# Nomi_s_Smart_Socket_V1.net
KiCad netlist of a schematic drawn in EAGLE
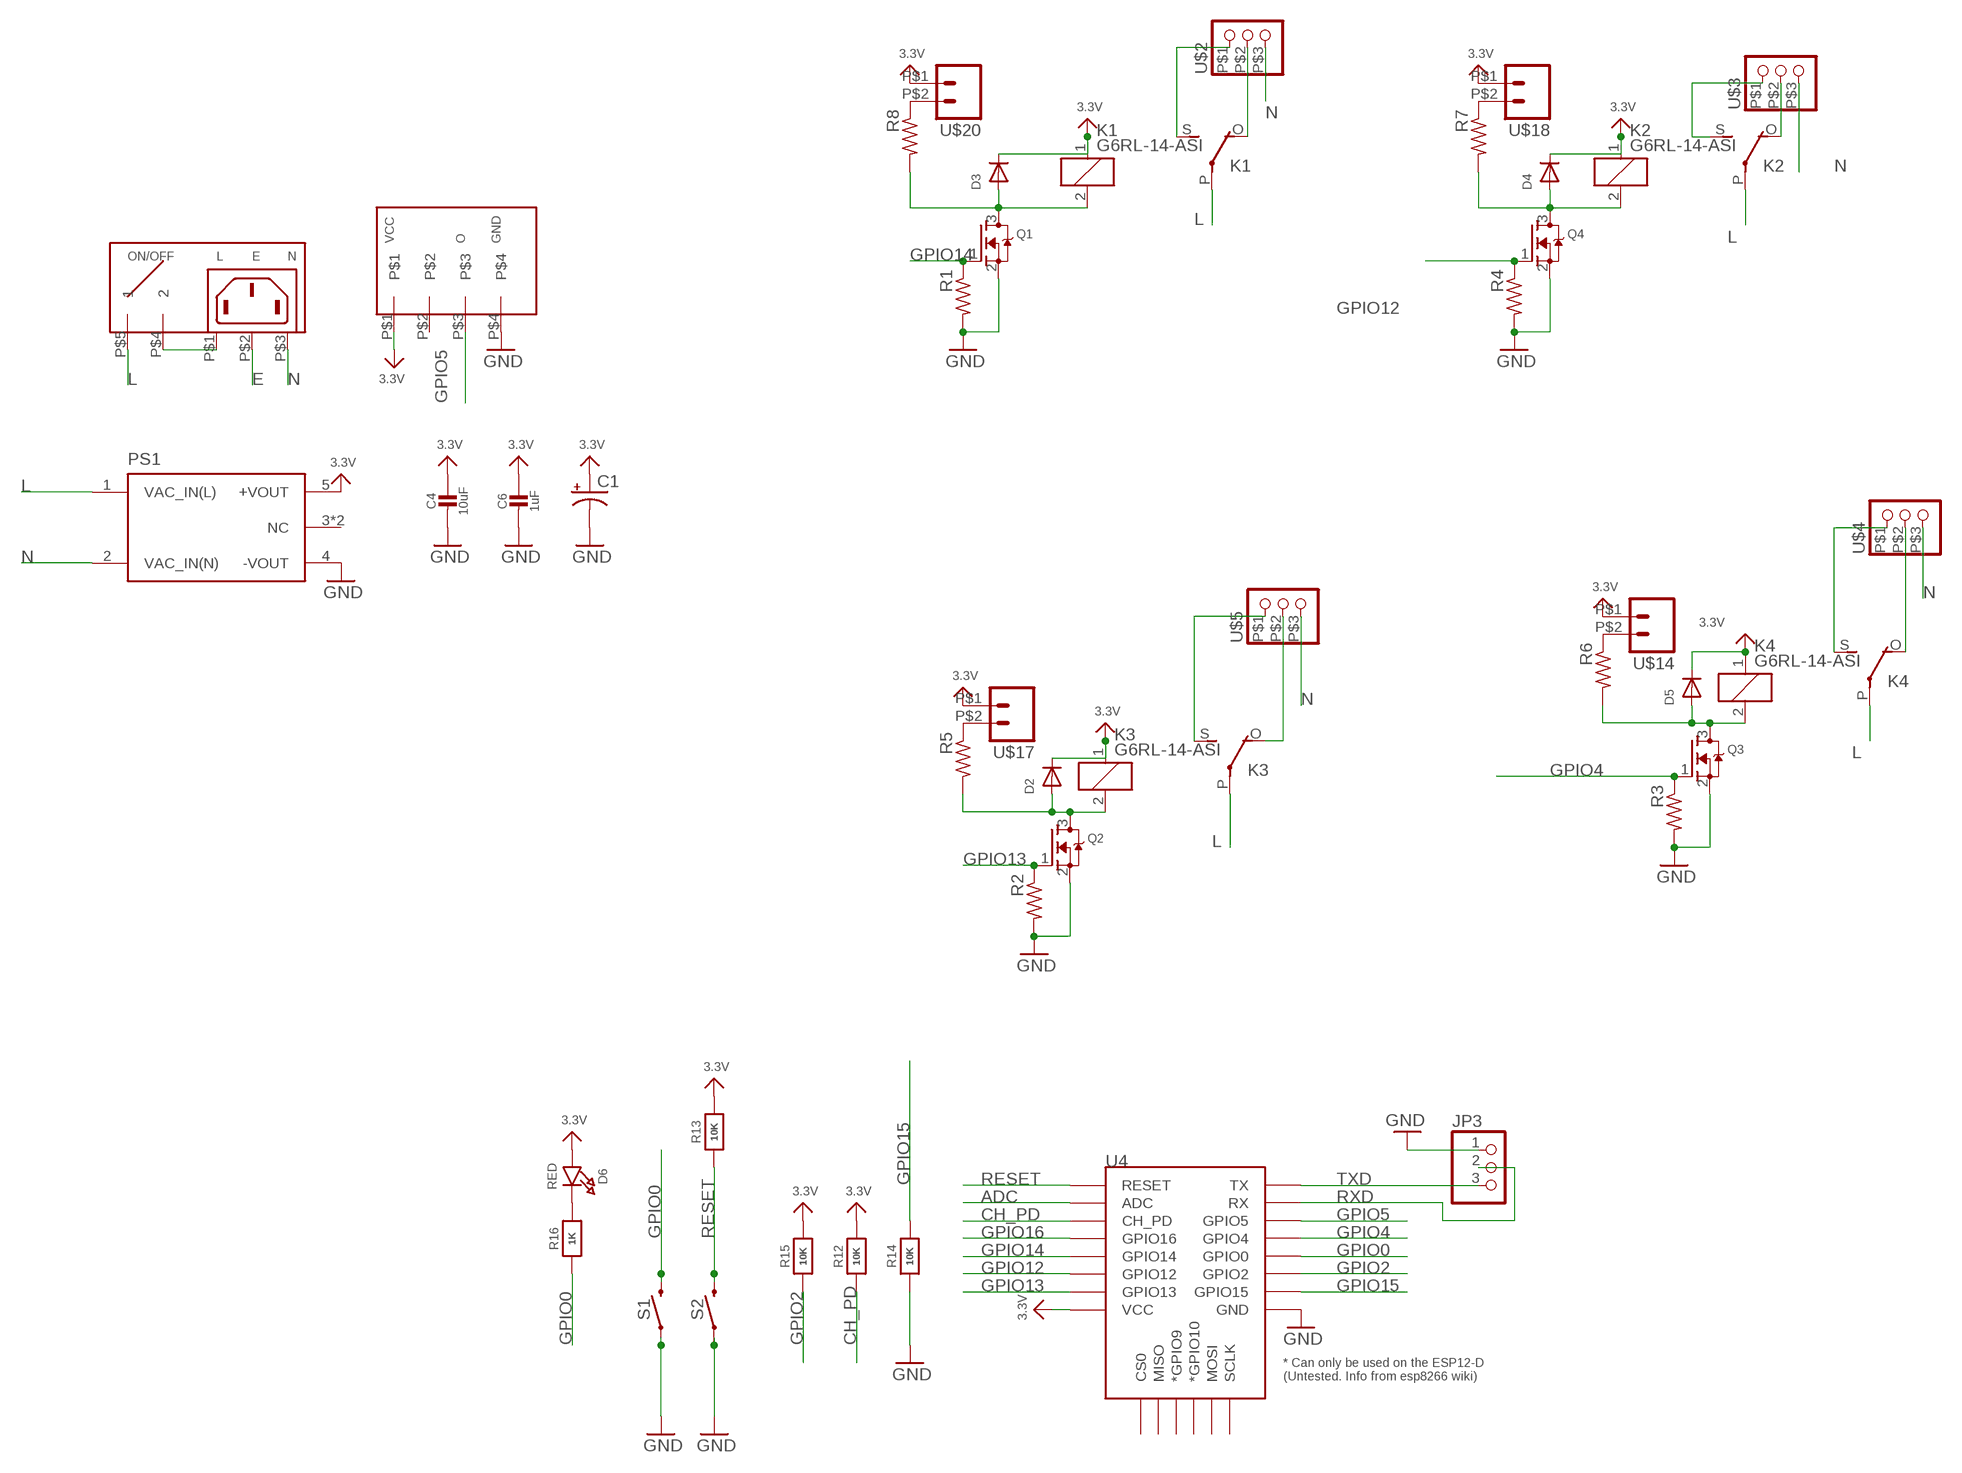
[diagram p0: schematic, sheet 1]

(export (version "E")
  (design (tool "Eeschema 10.0.6"))
  (components
    (comp (ref "C1")
      (value "CPOL-USE5-10.5")
      (footprint "eagle-import:E5-10,5")
      (libsource (lib "eagle-import") (part "CPOL-USE5-10.5"))
    )
    (comp (ref "C4")
      (value "10uF")
      (footprint "eagle-import:_0805")
      (libsource (lib "eagle-import") (part "CAP_CERAMIC_0805"))
    )
    (comp (ref "C6")
      (value "1uF")
      (footprint "eagle-import:_0603")
      (libsource (lib "eagle-import") (part "CAP_CERAMIC_0603"))
    )
    (comp (ref "D2")
      (value "DIODE_SOD-123FL")
      (footprint "eagle-import:SOD-123FL")
      (libsource (lib "eagle-import") (part "DIODE_SOD-123FL"))
    )
    (comp (ref "D3")
      (value "DIODE_SOD-123FL")
      (footprint "eagle-import:SOD-123FL")
      (libsource (lib "eagle-import") (part "DIODE_SOD-123FL"))
    )
    (comp (ref "D4")
      (value "DIODE_SOD-123FL")
      (footprint "eagle-import:SOD-123FL")
      (libsource (lib "eagle-import") (part "DIODE_SOD-123FL"))
    )
    (comp (ref "D5")
      (value "DIODE_SOD-123FL")
      (footprint "eagle-import:SOD-123FL")
      (libsource (lib "eagle-import") (part "DIODE_SOD-123FL"))
    )
    (comp (ref "D6")
      (value "RED")
      (footprint "eagle-import:CHIPLED_0805_NOOUTLINE")
      (libsource (lib "eagle-import") (part "LED0805_NOOUTLINE"))
    )
    (comp (ref "JP3")
      (value "PINHD-1X3")
      (footprint "eagle-import:1X03")
      (libsource (lib "eagle-import") (part "PINHD-1X3"))
    )
    (comp (ref "K1")
      (value "G6RL-14-ASI")
      (footprint "eagle-import:G6RW")
      (libsource (lib "eagle-import") (part "G6RL-14-ASI"))
    )
    (comp (ref "K2")
      (value "G6RL-14-ASI")
      (footprint "eagle-import:G6RW")
      (libsource (lib "eagle-import") (part "G6RL-14-ASI"))
    )
    (comp (ref "K3")
      (value "G6RL-14-ASI")
      (footprint "eagle-import:G6RW")
      (libsource (lib "eagle-import") (part "G6RL-14-ASI"))
    )
    (comp (ref "K4")
      (value "G6RL-14-ASI")
      (footprint "eagle-import:G6RW")
      (libsource (lib "eagle-import") (part "G6RL-14-ASI"))
    )
    (comp (ref "PS1")
      (value "RAC04-3.3SGBRAC04-3.3SGB-3D")
      (footprint "eagle-import:DIP1778W80P508L3670H1500Q6B")
      (libsource (lib "eagle-import") (part "RAC04-3.3SGBRAC04-3.3SGB-3D"))
    )
    (comp (ref "Q1")
      (value "MOSFET-NREFLOW")
      (footprint "eagle-import:SOT23")
      (libsource (lib "eagle-import") (part "MOSFET-NREFLOW"))
    )
    (comp (ref "Q2")
      (value "MOSFET-NREFLOW")
      (footprint "eagle-import:SOT23")
      (libsource (lib "eagle-import") (part "MOSFET-NREFLOW"))
    )
    (comp (ref "Q3")
      (value "MOSFET-NREFLOW")
      (footprint "eagle-import:SOT23")
      (libsource (lib "eagle-import") (part "MOSFET-NREFLOW"))
    )
    (comp (ref "Q4")
      (value "MOSFET-NREFLOW")
      (footprint "eagle-import:SOT23")
      (libsource (lib "eagle-import") (part "MOSFET-NREFLOW"))
    )
    (comp (ref "R1")
      (value "10k")
      (footprint "eagle-import:R0603")
      (libsource (lib "eagle-import") (part "R-US_R0603"))
    )
    (comp (ref "R2")
      (value "10k")
      (footprint "eagle-import:R0603")
      (libsource (lib "eagle-import") (part "R-US_R0603"))
    )
    (comp (ref "R3")
      (value "10k")
      (footprint "eagle-import:R0603")
      (libsource (lib "eagle-import") (part "R-US_R0603"))
    )
    (comp (ref "R4")
      (value "10k")
      (footprint "eagle-import:R0603")
      (libsource (lib "eagle-import") (part "R-US_R0603"))
    )
    (comp (ref "R5")
      (value "22")
      (footprint "eagle-import:R0603")
      (libsource (lib "eagle-import") (part "R-US_R0603"))
    )
    (comp (ref "R6")
      (value "22")
      (footprint "eagle-import:R0603")
      (libsource (lib "eagle-import") (part "R-US_R0603"))
    )
    (comp (ref "R7")
      (value "22")
      (footprint "eagle-import:R0603")
      (libsource (lib "eagle-import") (part "R-US_R0603"))
    )
    (comp (ref "R8")
      (value "22")
      (footprint "eagle-import:R0603")
      (libsource (lib "eagle-import") (part "R-US_R0603"))
    )
    (comp (ref "R12")
      (value "10K")
      (footprint "eagle-import:_0603")
      (libsource (lib "eagle-import") (part "RESISTOR_0603"))
    )
    (comp (ref "R13")
      (value "10K")
      (footprint "eagle-import:_0603")
      (libsource (lib "eagle-import") (part "RESISTOR_0603"))
    )
    (comp (ref "R14")
      (value "10K")
      (footprint "eagle-import:_0603")
      (libsource (lib "eagle-import") (part "RESISTOR_0603"))
    )
    (comp (ref "R15")
      (value "10K")
      (footprint "eagle-import:_0603")
      (libsource (lib "eagle-import") (part "RESISTOR_0603"))
    )
    (comp (ref "R16")
      (value "1K")
      (footprint "eagle-import:_0603")
      (libsource (lib "eagle-import") (part "RESISTOR_0603"))
    )
    (comp (ref "S1")
      (value "MOMENTARY-SWITCH-SPST-SMD-4.6X2.8MM")
      (footprint "eagle-import:TACTILE_SWITCH_SMD_4.6X2.8MM")
      (libsource (lib "eagle-import") (part "MOMENTARY-SWITCH-SPST-SMD-4.6X2.8MM"))
    )
    (comp (ref "S2")
      (value "MOMENTARY-SWITCH-SPST-SMD-4.6X2.8MM")
      (footprint "eagle-import:TACTILE_SWITCH_SMD_4.6X2.8MM")
      (libsource (lib "eagle-import") (part "MOMENTARY-SWITCH-SPST-SMD-4.6X2.8MM"))
    )
    (comp (ref "U$1")
      (value "AC-CONN-WITH-SWITCH")
      (footprint "eagle-import:AC-CONN-WITH-SWITCH")
      (libsource (lib "eagle-import") (part "AC-CONN-WITH-SWITCH"))
    )
    (comp (ref "U$2")
      (value "TERM-BLOCK-3POS-5MM5MM")
      (footprint "eagle-import:TERM-BLOCK-3POS-5MM")
      (libsource (lib "eagle-import") (part "TERM-BLOCK-3POS-5MM5MM"))
    )
    (comp (ref "U$3")
      (value "TERM-BLOCK-3POS-5MM5MM")
      (footprint "eagle-import:TERM-BLOCK-3POS-5MM")
      (libsource (lib "eagle-import") (part "TERM-BLOCK-3POS-5MM5MM"))
    )
    (comp (ref "U$4")
      (value "TERM-BLOCK-3POS-5MM5MM")
      (footprint "eagle-import:TERM-BLOCK-3POS-5MM")
      (libsource (lib "eagle-import") (part "TERM-BLOCK-3POS-5MM5MM"))
    )
    (comp (ref "U$5")
      (value "TERM-BLOCK-3POS-5MM5MM")
      (footprint "eagle-import:TERM-BLOCK-3POS-5MM")
      (libsource (lib "eagle-import") (part "TERM-BLOCK-3POS-5MM5MM"))
    )
    (comp (ref "U$13")
      (value "DHT22")
      (footprint "eagle-import:DHT22")
      (libsource (lib "eagle-import") (part "DHT22"))
    )
    (comp (ref "U$14")
      (value "TERMINAL-BLOCK-2POS-2.54MM")
      (footprint "eagle-import:TERMINAL-BLOCK-2POS-2.54MM")
      (libsource (lib "eagle-import") (part "TERMINAL-BLOCK-2POS-2.54MM"))
    )
    (comp (ref "U$17")
      (value "TERMINAL-BLOCK-2POS-2.54MM")
      (footprint "eagle-import:TERMINAL-BLOCK-2POS-2.54MM")
      (libsource (lib "eagle-import") (part "TERMINAL-BLOCK-2POS-2.54MM"))
    )
    (comp (ref "U$18")
      (value "TERMINAL-BLOCK-2POS-2.54MM")
      (footprint "eagle-import:TERMINAL-BLOCK-2POS-2.54MM")
      (libsource (lib "eagle-import") (part "TERMINAL-BLOCK-2POS-2.54MM"))
    )
    (comp (ref "U$20")
      (value "TERMINAL-BLOCK-2POS-2.54MM")
      (footprint "eagle-import:TERMINAL-BLOCK-2POS-2.54MM")
      (libsource (lib "eagle-import") (part "TERMINAL-BLOCK-2POS-2.54MM"))
    )
    (comp (ref "U4")
      (value "ESP12FSMD")
      (footprint "eagle-import:ESP12F")
      (libsource (lib "eagle-import") (part "ESP12FSMD"))
    )
  )
  (nets
    (net (code "1") (name "/ADC") (class "Default")
      (node (ref "U4") (pin "ADC") (pinfunction "ADC_ADC") (pintype "bidirectional"))
    )
    (net (code "2") (name "/CH_PD") (class "Default")
      (node (ref "R12") (pin "1") (pinfunction "1_1") (pintype "passive"))
      (node (ref "U4") (pin "EN") (pinfunction "CH_PD_EN") (pintype "bidirectional"))
    )
    (net (code "3") (name "/E") (class "Default")
      (node (ref "U$1") (pin "P$2") (pinfunction "EARTH_P$2") (pintype "passive"))
    )
    (net (code "4") (name "/GPIO0") (class "Default")
      (node (ref "R16") (pin "1") (pinfunction "1_1") (pintype "passive"))
      (node (ref "S1") (pin "3") (pinfunction "2_3") (pintype "passive"))
      (node (ref "S1") (pin "4") (pinfunction "2_4") (pintype "passive"))
      (node (ref "U4") (pin "GPIO0") (pinfunction "GPIO0_GPIO0") (pintype "bidirectional"))
    )
    (net (code "5") (name "/GPIO2") (class "Default")
      (node (ref "R15") (pin "1") (pinfunction "1_1") (pintype "passive"))
      (node (ref "U4") (pin "GPIO2") (pinfunction "GPIO2_GPIO2") (pintype "bidirectional"))
    )
    (net (code "6") (name "/GPIO4") (class "Default")
      (node (ref "Q3") (pin "1") (pinfunction "G_1") (pintype "bidirectional"))
      (node (ref "R3") (pin "1") (pinfunction "1_1") (pintype "passive"))
      (node (ref "U4") (pin "GPIO4") (pinfunction "GPIO4_GPIO4") (pintype "bidirectional"))
    )
    (net (code "7") (name "/GPIO5") (class "Default")
      (node (ref "U$13") (pin "P$3") (pinfunction "P$3_P$3") (pintype "bidirectional"))
      (node (ref "U4") (pin "GPIO5") (pinfunction "GPIO5_GPIO5") (pintype "bidirectional"))
    )
    (net (code "8") (name "/GPIO12") (class "Default")
      (node (ref "Q4") (pin "1") (pinfunction "G_1") (pintype "bidirectional"))
      (node (ref "R4") (pin "1") (pinfunction "1_1") (pintype "passive"))
      (node (ref "U4") (pin "GPIO12") (pinfunction "GPIO12_GPIO12") (pintype "bidirectional"))
    )
    (net (code "9") (name "/GPIO13") (class "Default")
      (node (ref "Q2") (pin "1") (pinfunction "G_1") (pintype "bidirectional"))
      (node (ref "R2") (pin "1") (pinfunction "1_1") (pintype "passive"))
      (node (ref "U4") (pin "GPIO13") (pinfunction "GPIO13_GPIO13") (pintype "bidirectional"))
    )
    (net (code "10") (name "/GPIO14") (class "Default")
      (node (ref "Q1") (pin "1") (pinfunction "G_1") (pintype "bidirectional"))
      (node (ref "R1") (pin "1") (pinfunction "1_1") (pintype "passive"))
      (node (ref "U4") (pin "GPIO14") (pinfunction "GPIO14_GPIO14") (pintype "bidirectional"))
    )
    (net (code "11") (name "/GPIO15") (class "Default")
      (node (ref "R14") (pin "2") (pinfunction "2_2") (pintype "passive"))
      (node (ref "U4") (pin "GPIO15") (pinfunction "GPIO15_GPIO15") (pintype "bidirectional"))
    )
    (net (code "12") (name "/GPIO16") (class "Default")
      (node (ref "U4") (pin "GPIO16") (pinfunction "GPIO16_GPIO16") (pintype "bidirectional"))
    )
    (net (code "13") (name "/L") (class "Default")
      (node (ref "K1") (pin "P") (pinfunction "P_P") (pintype "passive"))
      (node (ref "K2") (pin "P") (pinfunction "P_P") (pintype "passive"))
      (node (ref "K3") (pin "P") (pinfunction "P_P") (pintype "passive"))
      (node (ref "K4") (pin "P") (pinfunction "P_P") (pintype "passive"))
      (node (ref "PS1") (pin "1") (pinfunction "VAC_IN(L)_1") (pintype "input"))
      (node (ref "U$1") (pin "P$5") (pinfunction "1_P$5") (pintype "bidirectional"))
    )
    (net (code "14") (name "/N") (class "Default")
      (node (ref "PS1") (pin "2") (pinfunction "VAC_IN(N)_2") (pintype "input"))
      (node (ref "U$1") (pin "P$3") (pinfunction "N_P$3") (pintype "passive"))
      (node (ref "U$2") (pin "P$3") (pinfunction "3_P$3") (pintype "passive"))
      (node (ref "U$3") (pin "P$3") (pinfunction "3_P$3") (pintype "passive"))
      (node (ref "U$4") (pin "P$3") (pinfunction "3_P$3") (pintype "passive"))
      (node (ref "U$5") (pin "P$3") (pinfunction "3_P$3") (pintype "passive"))
    )
    (net (code "15") (name "/RESET") (class "Default")
      (node (ref "R13") (pin "1") (pinfunction "1_1") (pintype "passive"))
      (node (ref "S2") (pin "3") (pinfunction "2_3") (pintype "passive"))
      (node (ref "S2") (pin "4") (pinfunction "2_4") (pintype "passive"))
      (node (ref "U4") (pin "RST") (pinfunction "RESET_RST") (pintype "bidirectional"))
    )
    (net (code "16") (name "/RXD") (class "Default")
      (node (ref "JP3") (pin "2") (pinfunction "2_2") (pintype "passive"))
      (node (ref "U4") (pin "RXD") (pinfunction "RX_RXD") (pintype "bidirectional"))
    )
    (net (code "17") (name "/TXD") (class "Default")
      (node (ref "JP3") (pin "3") (pinfunction "3_3") (pintype "passive"))
      (node (ref "U4") (pin "TXD") (pinfunction "TX_TXD") (pintype "bidirectional"))
    )
    (net (code "18") (name "3.3V") (class "Default")
      (node (ref "C1") (pin "+") (pinfunction "+_+") (pintype "passive"))
      (node (ref "C4") (pin "1") (pinfunction "1_1") (pintype "passive"))
      (node (ref "C6") (pin "1") (pinfunction "1_1") (pintype "passive"))
      (node (ref "D2") (pin "C") (pinfunction "C_C") (pintype "passive"))
      (node (ref "D3") (pin "C") (pinfunction "C_C") (pintype "passive"))
      (node (ref "D4") (pin "C") (pinfunction "C_C") (pintype "passive"))
      (node (ref "D5") (pin "C") (pinfunction "C_C") (pintype "passive"))
      (node (ref "D6") (pin "A") (pinfunction "A_A") (pintype "passive"))
      (node (ref "K1") (pin "1") (pinfunction "1_1") (pintype "passive"))
      (node (ref "K2") (pin "1") (pinfunction "1_1") (pintype "passive"))
      (node (ref "K3") (pin "1") (pinfunction "1_1") (pintype "passive"))
      (node (ref "K4") (pin "1") (pinfunction "1_1") (pintype "passive"))
      (node (ref "PS1") (pin "5") (pinfunction "+VOUT_5") (pintype "output"))
      (node (ref "R12") (pin "2") (pinfunction "2_2") (pintype "passive"))
      (node (ref "R13") (pin "2") (pinfunction "2_2") (pintype "passive"))
      (node (ref "R15") (pin "2") (pinfunction "2_2") (pintype "passive"))
      (node (ref "U$13") (pin "P$1") (pinfunction "P$1_P$1") (pintype "bidirectional"))
      (node (ref "U$14") (pin "P$1") (pinfunction "1_P$1") (pintype "passive"))
      (node (ref "U$17") (pin "P$1") (pinfunction "1_P$1") (pintype "passive"))
      (node (ref "U$18") (pin "P$1") (pinfunction "1_P$1") (pintype "passive"))
      (node (ref "U$20") (pin "P$1") (pinfunction "1_P$1") (pintype "passive"))
      (node (ref "U4") (pin "3.3V") (pinfunction "VCC_3.3V") (pintype "bidirectional"))
    )
    (net (code "19") (name "GND") (class "Default")
      (node (ref "C1") (pin "-") (pinfunction "-_-") (pintype "passive"))
      (node (ref "C4") (pin "2") (pinfunction "2_2") (pintype "passive"))
      (node (ref "C6") (pin "2") (pinfunction "2_2") (pintype "passive"))
      (node (ref "JP3") (pin "1") (pinfunction "1_1") (pintype "passive"))
      (node (ref "PS1") (pin "4") (pinfunction "-VOUT_4") (pintype "output"))
      (node (ref "Q1") (pin "2") (pinfunction "S_2") (pintype "bidirectional"))
      (node (ref "Q2") (pin "2") (pinfunction "S_2") (pintype "bidirectional"))
      (node (ref "Q3") (pin "2") (pinfunction "S_2") (pintype "bidirectional"))
      (node (ref "Q4") (pin "2") (pinfunction "S_2") (pintype "bidirectional"))
      (node (ref "R1") (pin "2") (pinfunction "2_2") (pintype "passive"))
      (node (ref "R14") (pin "1") (pinfunction "1_1") (pintype "passive"))
      (node (ref "R2") (pin "2") (pinfunction "2_2") (pintype "passive"))
      (node (ref "R3") (pin "2") (pinfunction "2_2") (pintype "passive"))
      (node (ref "R4") (pin "2") (pinfunction "2_2") (pintype "passive"))
      (node (ref "S1") (pin "1") (pinfunction "1_1") (pintype "passive"))
      (node (ref "S1") (pin "2") (pinfunction "1_2") (pintype "passive"))
      (node (ref "S2") (pin "1") (pinfunction "1_1") (pintype "passive"))
      (node (ref "S2") (pin "2") (pinfunction "1_2") (pintype "passive"))
      (node (ref "U$13") (pin "P$4") (pinfunction "P$4_P$4") (pintype "bidirectional"))
      (node (ref "U4") (pin "GND") (pinfunction "GND_GND") (pintype "bidirectional"))
    )
    (net (code "20") (name "Net-(D6-PadC)") (class "Default")
      (node (ref "D6") (pin "C") (pinfunction "C_C") (pintype "passive"))
      (node (ref "R16") (pin "2") (pinfunction "2_2") (pintype "passive"))
    )
    (net (code "21") (name "Net-(Q1-D)") (class "Default")
      (node (ref "D3") (pin "A") (pinfunction "A_A") (pintype "passive"))
      (node (ref "K1") (pin "2") (pinfunction "2_2") (pintype "passive"))
      (node (ref "Q1") (pin "3") (pinfunction "D_3") (pintype "bidirectional"))
      (node (ref "R8") (pin "2") (pinfunction "2_2") (pintype "passive"))
    )
    (net (code "22") (name "Net-(Q2-D)") (class "Default")
      (node (ref "D2") (pin "A") (pinfunction "A_A") (pintype "passive"))
      (node (ref "K3") (pin "2") (pinfunction "2_2") (pintype "passive"))
      (node (ref "Q2") (pin "3") (pinfunction "D_3") (pintype "bidirectional"))
      (node (ref "R5") (pin "2") (pinfunction "2_2") (pintype "passive"))
    )
    (net (code "23") (name "Net-(Q3-D)") (class "Default")
      (node (ref "D5") (pin "A") (pinfunction "A_A") (pintype "passive"))
      (node (ref "K4") (pin "2") (pinfunction "2_2") (pintype "passive"))
      (node (ref "Q3") (pin "3") (pinfunction "D_3") (pintype "bidirectional"))
      (node (ref "R6") (pin "2") (pinfunction "2_2") (pintype "passive"))
    )
    (net (code "24") (name "Net-(Q4-D)") (class "Default")
      (node (ref "D4") (pin "A") (pinfunction "A_A") (pintype "passive"))
      (node (ref "K2") (pin "2") (pinfunction "2_2") (pintype "passive"))
      (node (ref "Q4") (pin "3") (pinfunction "D_3") (pintype "bidirectional"))
      (node (ref "R7") (pin "2") (pinfunction "2_2") (pintype "passive"))
    )
    (net (code "25") (name "Net-(U$1-2)") (class "Default")
      (node (ref "U$1") (pin "P$1") (pinfunction "L_P$1") (pintype "passive"))
      (node (ref "U$1") (pin "P$4") (pinfunction "2_P$4") (pintype "bidirectional"))
    )
    (net (code "26") (name "Net-(U$2-1)") (class "Default")
      (node (ref "K1") (pin "S") (pinfunction "S_S") (pintype "passive"))
      (node (ref "U$2") (pin "P$1") (pinfunction "1_P$1") (pintype "passive"))
    )
    (net (code "27") (name "Net-(U$2-2)") (class "Default")
      (node (ref "K1") (pin "O") (pinfunction "O_O") (pintype "passive"))
      (node (ref "U$2") (pin "P$2") (pinfunction "2_P$2") (pintype "passive"))
    )
    (net (code "28") (name "Net-(U$3-1)") (class "Default")
      (node (ref "K2") (pin "S") (pinfunction "S_S") (pintype "passive"))
      (node (ref "U$3") (pin "P$1") (pinfunction "1_P$1") (pintype "passive"))
    )
    (net (code "29") (name "Net-(U$3-2)") (class "Default")
      (node (ref "K2") (pin "O") (pinfunction "O_O") (pintype "passive"))
      (node (ref "U$3") (pin "P$2") (pinfunction "2_P$2") (pintype "passive"))
    )
    (net (code "30") (name "Net-(U$4-1)") (class "Default")
      (node (ref "K4") (pin "S") (pinfunction "S_S") (pintype "passive"))
      (node (ref "U$4") (pin "P$1") (pinfunction "1_P$1") (pintype "passive"))
    )
    (net (code "31") (name "Net-(U$4-2)") (class "Default")
      (node (ref "K4") (pin "O") (pinfunction "O_O") (pintype "passive"))
      (node (ref "U$4") (pin "P$2") (pinfunction "2_P$2") (pintype "passive"))
    )
    (net (code "32") (name "Net-(U$5-1)") (class "Default")
      (node (ref "K3") (pin "S") (pinfunction "S_S") (pintype "passive"))
      (node (ref "U$5") (pin "P$1") (pinfunction "1_P$1") (pintype "passive"))
    )
    (net (code "33") (name "Net-(U$5-2)") (class "Default")
      (node (ref "K3") (pin "O") (pinfunction "O_O") (pintype "passive"))
      (node (ref "U$5") (pin "P$2") (pinfunction "2_P$2") (pintype "passive"))
    )
    (net (code "34") (name "Net-(U$14-2)") (class "Default")
      (node (ref "R6") (pin "1") (pinfunction "1_1") (pintype "passive"))
      (node (ref "U$14") (pin "P$2") (pinfunction "2_P$2") (pintype "passive"))
    )
    (net (code "35") (name "Net-(U$17-2)") (class "Default")
      (node (ref "R5") (pin "1") (pinfunction "1_1") (pintype "passive"))
      (node (ref "U$17") (pin "P$2") (pinfunction "2_P$2") (pintype "passive"))
    )
    (net (code "36") (name "Net-(U$18-2)") (class "Default")
      (node (ref "R7") (pin "1") (pinfunction "1_1") (pintype "passive"))
      (node (ref "U$18") (pin "P$2") (pinfunction "2_P$2") (pintype "passive"))
    )
    (net (code "37") (name "Net-(U$20-2)") (class "Default")
      (node (ref "R8") (pin "1") (pinfunction "1_1") (pintype "passive"))
      (node (ref "U$20") (pin "P$2") (pinfunction "2_P$2") (pintype "passive"))
    )
    (net (code "38") (name "unconnected-(PS1-NC-Pad3)") (class "Default")
      (node (ref "PS1") (pin "3") (pinfunction "NC_3") (pintype "no_connect"))
    )
    (net (code "39") (name "unconnected-(PS1-NC-Pad6)") (class "Default")
      (node (ref "PS1") (pin "6") (pinfunction "NC_6") (pintype "no_connect"))
    )
    (net (code "40") (name "unconnected-(U$13-PadP$2)") (class "Default")
      (node (ref "U$13") (pin "P$2") (pinfunction "P$2_P$2") (pintype "bidirectional"))
    )
    (net (code "41") (name "unconnected-(U4-*GPIO9-PadGPIO9)") (class "Default")
      (node (ref "U4") (pin "GPIO9") (pinfunction "*GPIO9_GPIO9") (pintype "bidirectional"))
    )
    (net (code "42") (name "unconnected-(U4-*GPIO10-PadGPIO10)") (class "Default")
      (node (ref "U4") (pin "GPIO10") (pinfunction "*GPIO10_GPIO10") (pintype "bidirectional"))
    )
    (net (code "43") (name "unconnected-(U4-PadCS0)") (class "Default")
      (node (ref "U4") (pin "CS0") (pinfunction "CS0_CS0") (pintype "bidirectional"))
    )
    (net (code "44") (name "unconnected-(U4-PadMISO)") (class "Default")
      (node (ref "U4") (pin "MISO") (pinfunction "MISO_MISO") (pintype "bidirectional"))
    )
    (net (code "45") (name "unconnected-(U4-PadMOSI)") (class "Default")
      (node (ref "U4") (pin "MOSI") (pinfunction "MOSI_MOSI") (pintype "bidirectional"))
    )
    (net (code "46") (name "unconnected-(U4-SCLK-PadCLK)") (class "Default")
      (node (ref "U4") (pin "CLK") (pinfunction "SCLK_CLK") (pintype "bidirectional"))
    )
  )
)
